# DS8_SCHEMATICv0_1.net
KiCad netlist of a schematic drawn in EAGLE
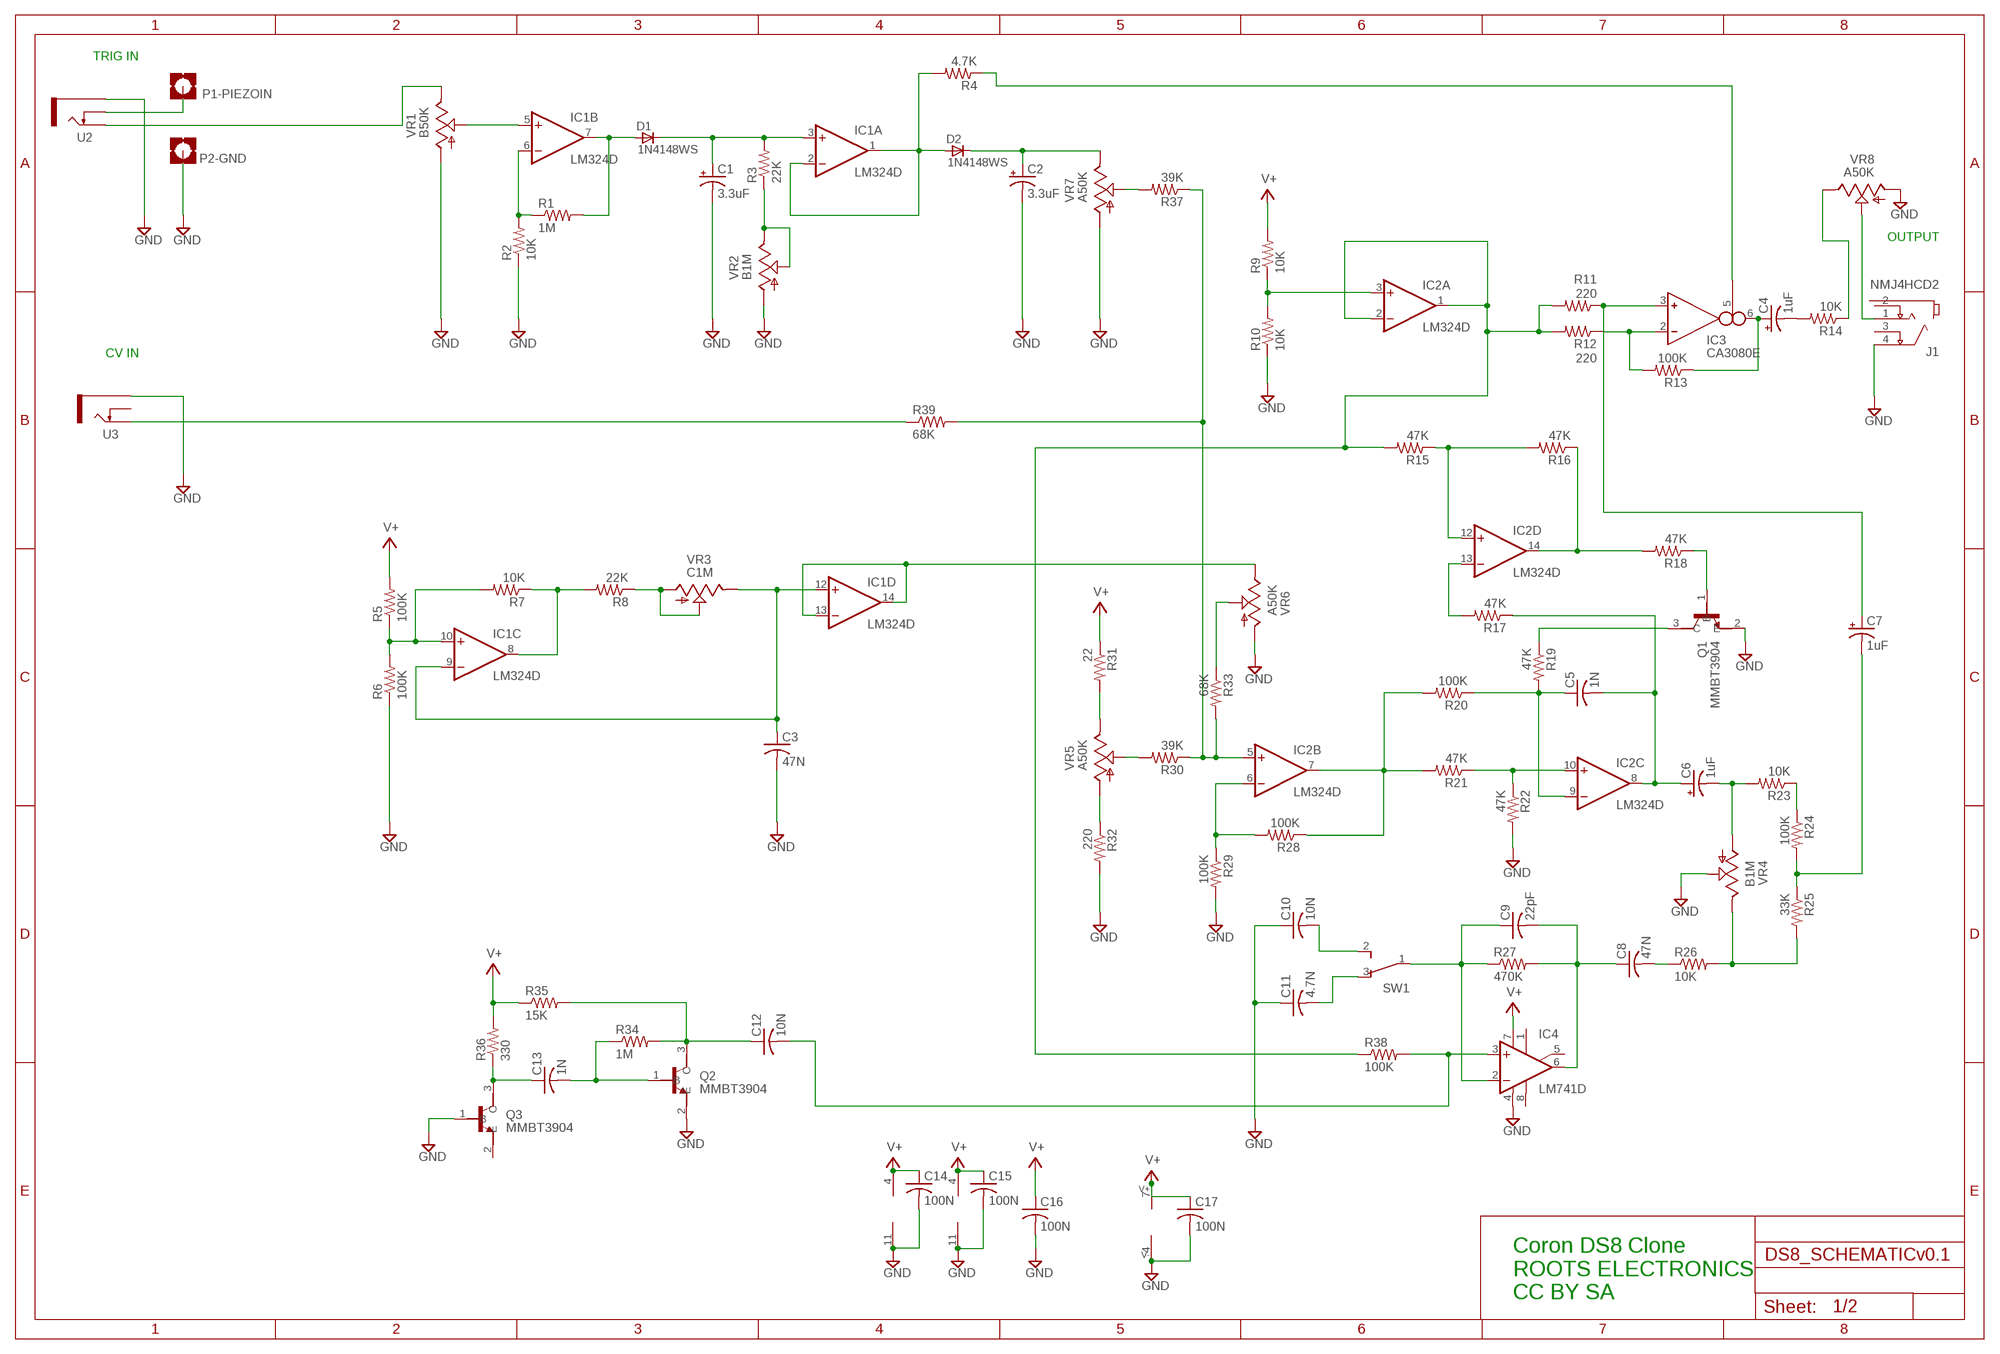
[diagram p0: schematic, sheet 1]
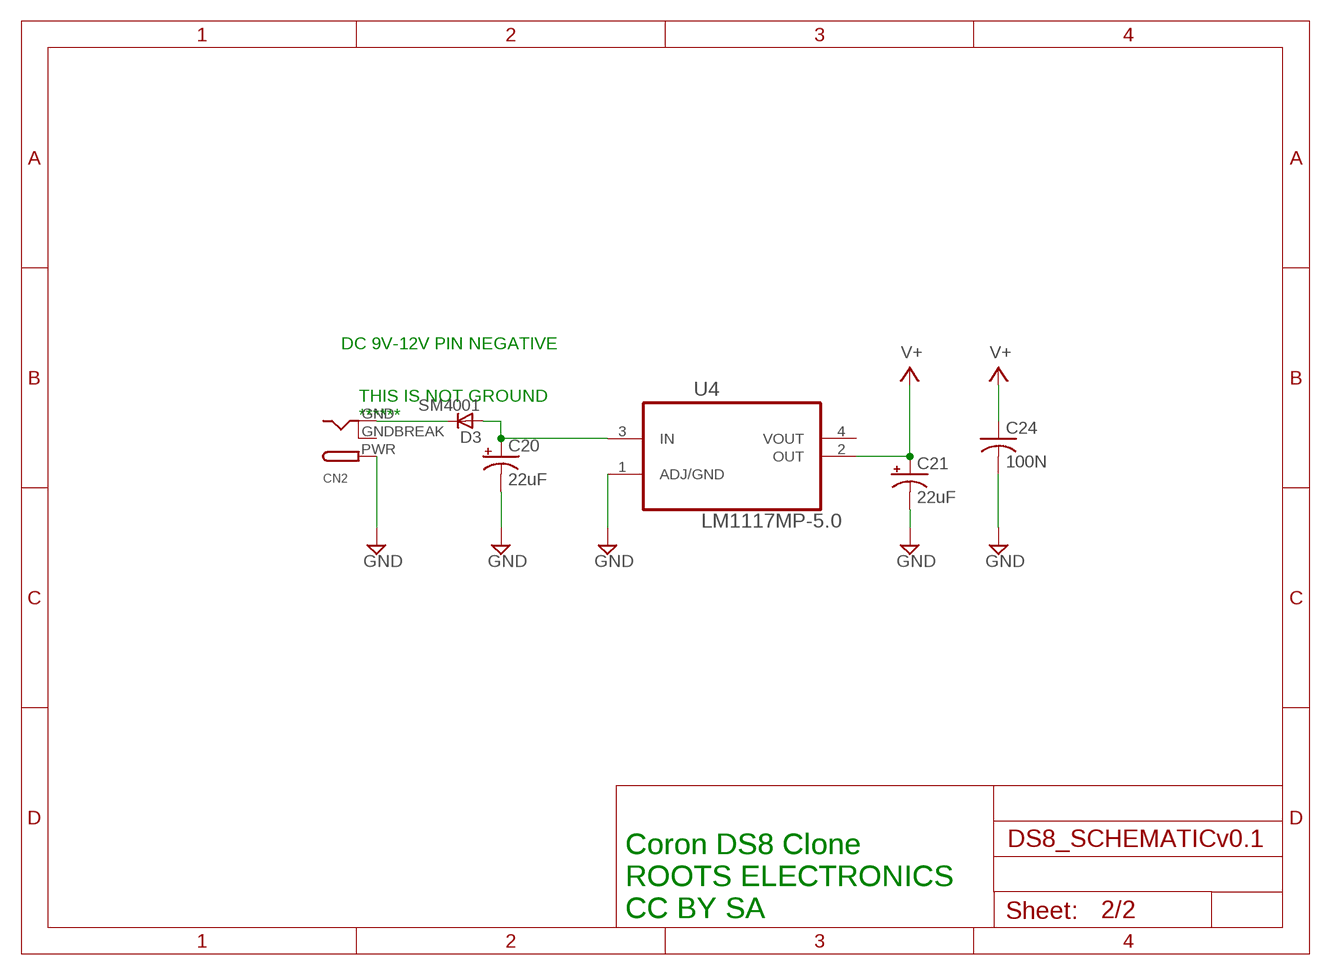
[diagram p1: schematic, sheet 2]

(export (version "E")
  (design (tool "Eeschema 10.0.6"))
  (components
    (comp (ref "C1")
      (value "3.3uF")
      (footprint "eagle-import:PANASONIC_C")
      (libsource (lib "eagle-import") (part "CPOL-USC"))
    )
    (comp (ref "C2")
      (value "3.3uF")
      (footprint "eagle-import:PANASONIC_C")
      (libsource (lib "eagle-import") (part "CPOL-USC"))
    )
    (comp (ref "C3")
      (value "47N")
      (footprint "eagle-import:C0603")
      (libsource (lib "eagle-import") (part "C-USC0603"))
    )
    (comp (ref "C4")
      (value "1uF")
      (footprint "eagle-import:PANASONIC_B")
      (libsource (lib "eagle-import") (part "CPOL-USB"))
    )
    (comp (ref "C5")
      (value "1N")
      (footprint "eagle-import:C0603")
      (libsource (lib "eagle-import") (part "C-USC0603"))
    )
    (comp (ref "C6")
      (value "1uF")
      (footprint "eagle-import:PANASONIC_B")
      (libsource (lib "eagle-import") (part "CPOL-USB"))
    )
    (comp (ref "C7")
      (value "1uF")
      (footprint "eagle-import:PANASONIC_B")
      (libsource (lib "eagle-import") (part "CPOL-USB"))
    )
    (comp (ref "C8")
      (value "47N")
      (footprint "eagle-import:C0603")
      (libsource (lib "eagle-import") (part "C-USC0603"))
    )
    (comp (ref "C9")
      (value "22pF")
      (footprint "eagle-import:C0603")
      (libsource (lib "eagle-import") (part "C-USC0603"))
    )
    (comp (ref "C10")
      (value "10N")
      (footprint "eagle-import:C0603")
      (libsource (lib "eagle-import") (part "C-USC0603"))
    )
    (comp (ref "C11")
      (value "4.7N")
      (footprint "eagle-import:C0603")
      (libsource (lib "eagle-import") (part "C-USC0603"))
    )
    (comp (ref "C12")
      (value "10N")
      (footprint "eagle-import:C0603")
      (libsource (lib "eagle-import") (part "C-USC0603"))
    )
    (comp (ref "C13")
      (value "1N")
      (footprint "eagle-import:C0603")
      (libsource (lib "eagle-import") (part "C-USC0603"))
    )
    (comp (ref "C14")
      (value "100N")
      (footprint "eagle-import:C0603")
      (libsource (lib "eagle-import") (part "C-USC0603"))
    )
    (comp (ref "C15")
      (value "100N")
      (footprint "eagle-import:C0603")
      (libsource (lib "eagle-import") (part "C-USC0603"))
    )
    (comp (ref "C16")
      (value "100N")
      (footprint "eagle-import:C0603")
      (libsource (lib "eagle-import") (part "C-USC0603"))
    )
    (comp (ref "C17")
      (value "100N")
      (footprint "eagle-import:C0603")
      (libsource (lib "eagle-import") (part "C-USC0603"))
    )
    (comp (ref "D1")
      (value "1N4148WS")
      (footprint "eagle-import:SOD323F")
      (libsource (lib "eagle-import") (part "1N4148WS"))
    )
    (comp (ref "D2")
      (value "1N4148WS")
      (footprint "eagle-import:SOD323F")
      (libsource (lib "eagle-import") (part "1N4148WS"))
    )
    (comp (ref "IC1")
      (value "LM324D")
      (footprint "eagle-import:SO14")
      (libsource (lib "eagle-import") (part "LM324D"))
    )
    (comp (ref "IC2")
      (value "LM324D")
      (footprint "eagle-import:SO14")
      (libsource (lib "eagle-import") (part "LM324D"))
    )
    (comp (ref "IC3")
      (value "CA3080E")
      (footprint "eagle-import:DIL08")
      (libsource (lib "eagle-import") (part "CA3080E"))
    )
    (comp (ref "IC4")
      (value "LM741D")
      (footprint "eagle-import:SO08")
      (libsource (lib "eagle-import") (part "741DLM"))
    )
    (comp (ref "J1")
      (value "NMJ4HCD2")
      (footprint "eagle-import:NEUTRIK_NMJ4HCD2")
      (fields (field (name "MF") "Neutrik"))
      (libsource (lib "eagle-import") (part "NMJ4HCD2"))
    )
    (comp (ref "P1-PIEZOIN")
      (value "MOUNT-PAD-SQUARE2.8")
      (footprint "eagle-import:2,8-PAD-SQUARE")
      (libsource (lib "eagle-import") (part "MOUNT-PAD-SQUARE2.8"))
    )
    (comp (ref "P2-GND")
      (value "MOUNT-PAD-SQUARE2.8")
      (footprint "eagle-import:2,8-PAD-SQUARE")
      (libsource (lib "eagle-import") (part "MOUNT-PAD-SQUARE2.8"))
    )
    (comp (ref "Q1")
      (value "MMBT3904")
      (footprint "eagle-import:SOT95P240X120-3N")
      (fields (field (name "MF") "STMicroelectronics"))
      (libsource (lib "eagle-import") (part "MMBT3904"))
    )
    (comp (ref "Q2")
      (value "MMBT3904")
      (footprint "eagle-import:SOT95P240X120-3N")
      (fields (field (name "MF") "STMicroelectronics"))
      (libsource (lib "eagle-import") (part "MMBT3904"))
    )
    (comp (ref "Q3")
      (value "MMBT3904")
      (footprint "eagle-import:SOT95P240X120-3N")
      (fields (field (name "MF") "STMicroelectronics"))
      (libsource (lib "eagle-import") (part "MMBT3904"))
    )
    (comp (ref "R1")
      (value "1M")
      (footprint "eagle-import:R0603")
      (libsource (lib "eagle-import") (part "R-US_R0603"))
    )
    (comp (ref "R2")
      (value "10K")
      (footprint "eagle-import:R0603")
      (libsource (lib "eagle-import") (part "R-US_R0603"))
    )
    (comp (ref "R3")
      (value "22K")
      (footprint "eagle-import:R0603")
      (libsource (lib "eagle-import") (part "R-US_R0603"))
    )
    (comp (ref "R4")
      (value "4.7K")
      (footprint "eagle-import:R0603")
      (libsource (lib "eagle-import") (part "R-US_R0603"))
    )
    (comp (ref "R5")
      (value "100K")
      (footprint "eagle-import:R0603")
      (libsource (lib "eagle-import") (part "R-US_R0603"))
    )
    (comp (ref "R6")
      (value "100K")
      (footprint "eagle-import:R0603")
      (libsource (lib "eagle-import") (part "R-US_R0603"))
    )
    (comp (ref "R7")
      (value "10K")
      (footprint "eagle-import:R0603")
      (libsource (lib "eagle-import") (part "R-US_R0603"))
    )
    (comp (ref "R8")
      (value "22K")
      (footprint "eagle-import:R0603")
      (libsource (lib "eagle-import") (part "R-US_R0603"))
    )
    (comp (ref "R9")
      (value "10K")
      (footprint "eagle-import:R0603")
      (libsource (lib "eagle-import") (part "R-US_R0603"))
    )
    (comp (ref "R10")
      (value "10K")
      (footprint "eagle-import:R0603")
      (libsource (lib "eagle-import") (part "R-US_R0603"))
    )
    (comp (ref "R11")
      (value "220")
      (footprint "eagle-import:R0603")
      (libsource (lib "eagle-import") (part "R-US_R0603"))
    )
    (comp (ref "R12")
      (value "220")
      (footprint "eagle-import:R0603")
      (libsource (lib "eagle-import") (part "R-US_R0603"))
    )
    (comp (ref "R13")
      (value "100K")
      (footprint "eagle-import:R0603")
      (libsource (lib "eagle-import") (part "R-US_R0603"))
    )
    (comp (ref "R14")
      (value "10K")
      (footprint "eagle-import:R0603")
      (libsource (lib "eagle-import") (part "R-US_R0603"))
    )
    (comp (ref "R15")
      (value "47K")
      (footprint "eagle-import:R0603")
      (libsource (lib "eagle-import") (part "R-US_R0603"))
    )
    (comp (ref "R16")
      (value "47K")
      (footprint "eagle-import:R0603")
      (libsource (lib "eagle-import") (part "R-US_R0603"))
    )
    (comp (ref "R17")
      (value "47K")
      (footprint "eagle-import:R0603")
      (libsource (lib "eagle-import") (part "R-US_R0603"))
    )
    (comp (ref "R18")
      (value "47K")
      (footprint "eagle-import:R0603")
      (libsource (lib "eagle-import") (part "R-US_R0603"))
    )
    (comp (ref "R19")
      (value "47K")
      (footprint "eagle-import:R0603")
      (libsource (lib "eagle-import") (part "R-US_R0603"))
    )
    (comp (ref "R20")
      (value "100K")
      (footprint "eagle-import:R0603")
      (libsource (lib "eagle-import") (part "R-US_R0603"))
    )
    (comp (ref "R21")
      (value "47K")
      (footprint "eagle-import:R0603")
      (libsource (lib "eagle-import") (part "R-US_R0603"))
    )
    (comp (ref "R22")
      (value "47K")
      (footprint "eagle-import:R0603")
      (libsource (lib "eagle-import") (part "R-US_R0603"))
    )
    (comp (ref "R23")
      (value "10K")
      (footprint "eagle-import:R0603")
      (libsource (lib "eagle-import") (part "R-US_R0603"))
    )
    (comp (ref "R24")
      (value "100K")
      (footprint "eagle-import:R0603")
      (libsource (lib "eagle-import") (part "R-US_R0603"))
    )
    (comp (ref "R25")
      (value "33K")
      (footprint "eagle-import:R0603")
      (libsource (lib "eagle-import") (part "R-US_R0603"))
    )
    (comp (ref "R26")
      (value "10K")
      (footprint "eagle-import:R0603")
      (libsource (lib "eagle-import") (part "R-US_R0603"))
    )
    (comp (ref "R27")
      (value "470K")
      (footprint "eagle-import:R0603")
      (libsource (lib "eagle-import") (part "R-US_R0603"))
    )
    (comp (ref "R28")
      (value "100K")
      (footprint "eagle-import:R0603")
      (libsource (lib "eagle-import") (part "R-US_R0603"))
    )
    (comp (ref "R29")
      (value "100K")
      (footprint "eagle-import:R0603")
      (libsource (lib "eagle-import") (part "R-US_R0603"))
    )
    (comp (ref "R30")
      (value "39K")
      (footprint "eagle-import:R0603")
      (libsource (lib "eagle-import") (part "R-US_R0603"))
    )
    (comp (ref "R31")
      (value "22")
      (footprint "eagle-import:R0603")
      (libsource (lib "eagle-import") (part "R-US_R0603"))
    )
    (comp (ref "R32")
      (value "220")
      (footprint "eagle-import:R0603")
      (libsource (lib "eagle-import") (part "R-US_R0603"))
    )
    (comp (ref "R33")
      (value "68K")
      (footprint "eagle-import:R0603")
      (libsource (lib "eagle-import") (part "R-US_R0603"))
    )
    (comp (ref "R34")
      (value "1M")
      (footprint "eagle-import:R0603")
      (libsource (lib "eagle-import") (part "R-US_R0603"))
    )
    (comp (ref "R35")
      (value "15K")
      (footprint "eagle-import:R0603")
      (libsource (lib "eagle-import") (part "R-US_R0603"))
    )
    (comp (ref "R36")
      (value "330")
      (footprint "eagle-import:R0603")
      (libsource (lib "eagle-import") (part "R-US_R0603"))
    )
    (comp (ref "R37")
      (value "39K")
      (footprint "eagle-import:R0603")
      (libsource (lib "eagle-import") (part "R-US_R0603"))
    )
    (comp (ref "R38")
      (value "100K")
      (footprint "eagle-import:R0603")
      (libsource (lib "eagle-import") (part "R-US_R0603"))
    )
    (comp (ref "R39")
      (value "68K")
      (footprint "eagle-import:R0603")
      (libsource (lib "eagle-import") (part "R-US_R0603"))
    )
    (comp (ref "SW1")
      (value "450301014042")
      (footprint "eagle-import:450301014042")
      (libsource (lib "eagle-import") (part "450301014042"))
    )
    (comp (ref "U2")
      (value "THONKICONNNEW")
      (footprint "eagle-import:WQP-PJ301M-12_JACK")
      (libsource (lib "eagle-import") (part "THONKICONNNEW"))
    )
    (comp (ref "U3")
      (value "THONKICONNNEW")
      (footprint "eagle-import:WQP-PJ301M-12_JACK")
      (libsource (lib "eagle-import") (part "THONKICONNNEW"))
    )
    (comp (ref "VR1")
      (value "B50K")
      (footprint "eagle-import:9MM_SNAP-IN_POT")
      (libsource (lib "eagle-import") (part "9MM_SNAP-IN_POT_"))
    )
    (comp (ref "VR2")
      (value "B1M")
      (footprint "eagle-import:9MM_SNAP-IN_POT")
      (libsource (lib "eagle-import") (part "9MM_SNAP-IN_POT_"))
    )
    (comp (ref "VR3")
      (value "C1M")
      (footprint "eagle-import:9MM_SNAP-IN_POT")
      (libsource (lib "eagle-import") (part "9MM_SNAP-IN_POT_"))
    )
    (comp (ref "VR4")
      (value "B1M")
      (footprint "eagle-import:9MM_SNAP-IN_POT")
      (libsource (lib "eagle-import") (part "9MM_SNAP-IN_POT_"))
    )
    (comp (ref "VR5")
      (value "A50K")
      (footprint "eagle-import:9MM_SNAP-IN_POT")
      (libsource (lib "eagle-import") (part "9MM_SNAP-IN_POT_"))
    )
    (comp (ref "VR6")
      (value "A50K")
      (footprint "eagle-import:9MM_SNAP-IN_POT")
      (libsource (lib "eagle-import") (part "9MM_SNAP-IN_POT_"))
    )
    (comp (ref "VR7")
      (value "A50K")
      (footprint "eagle-import:9MM_SNAP-IN_POT")
      (libsource (lib "eagle-import") (part "9MM_SNAP-IN_POT_"))
    )
    (comp (ref "VR8")
      (value "A50K")
      (footprint "eagle-import:9MM_SNAP-IN_POT")
      (libsource (lib "eagle-import") (part "9MM_SNAP-IN_POT_"))
    )
    (comp (ref "C20")
      (value "22uF")
      (footprint "eagle-import:PANASONIC_C")
      (libsource (lib "eagle-import") (part "CPOL-USC"))
    )
    (comp (ref "C21")
      (value "22uF")
      (footprint "eagle-import:PANASONIC_C")
      (libsource (lib "eagle-import") (part "CPOL-USC"))
    )
    (comp (ref "C24")
      (value "100N")
      (footprint "eagle-import:C0603")
      (libsource (lib "eagle-import") (part "C-USC0603"))
    )
    (comp (ref "CN2")
      (value "DCBARRELPTH")
      (footprint "eagle-import:DCJACK_2MM_PTH")
      (libsource (lib "eagle-import") (part "DCBARRELPTH"))
    )
    (comp (ref "D3")
      (value "SM4001")
      (footprint "eagle-import:MELF-MLL41_DO213AB")
      (libsource (lib "eagle-import") (part "SM4001"))
    )
    (comp (ref "U4")
      (value "LM1117MP-5.0")
      (footprint "eagle-import:SOT230P696X180-4N")
      (fields (field (name "MF") "Texas Instruments"))
      (libsource (lib "eagle-import") (part "LM1117MP-5.0"))
    )
  )
  (nets
    (net (code "1") (name "GND") (class "Default")
      (node (ref "C1") (pin "-") (pinfunction "-_-") (pintype "passive"))
      (node (ref "C10") (pin "1") (pinfunction "1_1") (pintype "passive"))
      (node (ref "C11") (pin "1") (pinfunction "1_1") (pintype "passive"))
      (node (ref "C14") (pin "2") (pinfunction "2_2") (pintype "passive"))
      (node (ref "C15") (pin "2") (pinfunction "2_2") (pintype "passive"))
      (node (ref "C16") (pin "2") (pinfunction "2_2") (pintype "passive"))
      (node (ref "C17") (pin "2") (pinfunction "2_2") (pintype "passive"))
      (node (ref "C2") (pin "-") (pinfunction "-_-") (pintype "passive"))
      (node (ref "C20") (pin "-") (pinfunction "-_-") (pintype "passive"))
      (node (ref "C21") (pin "-") (pinfunction "-_-") (pintype "passive"))
      (node (ref "C24") (pin "2") (pinfunction "2_2") (pintype "passive"))
      (node (ref "C3") (pin "2") (pinfunction "2_2") (pintype "passive"))
      (node (ref "CN2") (pin "PWR") (pinfunction "PWR_PWR") (pintype "power_in"))
      (node (ref "IC1") (pin "11") (pinfunction "V-_11") (pintype "power_in"))
      (node (ref "IC2") (pin "11") (pinfunction "V-_11") (pintype "power_in"))
      (node (ref "IC3") (pin "4") (pinfunction "V-_4") (pintype "power_in"))
      (node (ref "IC4") (pin "4") (pinfunction "V-_4") (pintype "power_in"))
      (node (ref "J1") (pin "4") (pinfunction "S_4") (pintype "passive"))
      (node (ref "P2-GND") (pin "B2,8") (pinfunction "MOUNT_B2,8") (pintype "passive"))
      (node (ref "Q1") (pin "2") (pinfunction "E_2") (pintype "passive"))
      (node (ref "Q2") (pin "2") (pinfunction "E_2") (pintype "passive"))
      (node (ref "Q3") (pin "1") (pinfunction "B_1") (pintype "passive"))
      (node (ref "R10") (pin "1") (pinfunction "1_1") (pintype "passive"))
      (node (ref "R2") (pin "1") (pinfunction "1_1") (pintype "passive"))
      (node (ref "R22") (pin "2") (pinfunction "2_2") (pintype "passive"))
      (node (ref "R29") (pin "2") (pinfunction "2_2") (pintype "passive"))
      (node (ref "R32") (pin "2") (pinfunction "2_2") (pintype "passive"))
      (node (ref "R6") (pin "1") (pinfunction "1_1") (pintype "passive"))
      (node (ref "U2") (pin "P$3_SLEEVE") (pinfunction "SLEEVE_P$3_SLEEVE") (pintype "passive"))
      (node (ref "U3") (pin "P$3_SLEEVE") (pinfunction "SLEEVE_P$3_SLEEVE") (pintype "passive"))
      (node (ref "U4") (pin "1") (pinfunction "ADJ/GND_1") (pintype "passive"))
      (node (ref "VR1") (pin "1") (pinfunction "A_1") (pintype "passive"))
      (node (ref "VR2") (pin "1") (pinfunction "A_1") (pintype "passive"))
      (node (ref "VR4") (pin "2") (pinfunction "S_2") (pintype "passive"))
      (node (ref "VR6") (pin "1") (pinfunction "A_1") (pintype "passive"))
      (node (ref "VR7") (pin "1") (pinfunction "A_1") (pintype "passive"))
      (node (ref "VR8") (pin "1") (pinfunction "A_1") (pintype "passive"))
    )
    (net (code "2") (name "GNDBREAK") (class "Default")
      (node (ref "CN2") (pin "GNDBREAK") (pinfunction "GNDBREAK_GNDBREAK") (pintype "power_in"))
    )
    (net (code "3") (name "Net-(C4-Pad-)") (class "Default")
      (node (ref "C4") (pin "-") (pinfunction "-_-") (pintype "passive"))
      (node (ref "R14") (pin "2") (pinfunction "2_2") (pintype "passive"))
    )
    (net (code "4") (name "Net-(C7-Pad-)") (class "Default")
      (node (ref "C7") (pin "-") (pinfunction "-_-") (pintype "passive"))
      (node (ref "R24") (pin "2") (pinfunction "2_2") (pintype "passive"))
      (node (ref "R25") (pin "1") (pinfunction "1_1") (pintype "passive"))
    )
    (net (code "5") (name "Net-(C8-Pad2)") (class "Default")
      (node (ref "C8") (pin "2") (pinfunction "2_2") (pintype "passive"))
      (node (ref "R26") (pin "1") (pinfunction "1_1") (pintype "passive"))
    )
    (net (code "6") (name "Net-(C10-Pad2)") (class "Default")
      (node (ref "C10") (pin "2") (pinfunction "2_2") (pintype "passive"))
      (node (ref "SW1") (pin "2") (pinfunction "2_2") (pintype "passive"))
    )
    (net (code "7") (name "Net-(C11-Pad2)") (class "Default")
      (node (ref "C11") (pin "2") (pinfunction "2_2") (pintype "passive"))
      (node (ref "SW1") (pin "3") (pinfunction "3_3") (pintype "passive"))
    )
    (net (code "8") (name "Net-(CN2-PadGND)") (class "Default")
      (node (ref "CN2") (pin "GND") (pinfunction "GND_GND") (pintype "power_in"))
      (node (ref "D3") (pin "C") (pinfunction "C_C") (pintype "passive"))
    )
    (net (code "9") (name "Net-(IC1A-+IN)") (class "Default")
      (node (ref "C1") (pin "+") (pinfunction "+_+") (pintype "passive"))
      (node (ref "D1") (pin "C") (pinfunction "C_C") (pintype "passive"))
      (node (ref "IC1") (pin "3") (pinfunction "+IN_3") (pintype "input"))
      (node (ref "R3") (pin "2") (pinfunction "2_2") (pintype "passive"))
    )
    (net (code "10") (name "Net-(IC1A--IN)") (class "Default")
      (node (ref "D2") (pin "A") (pinfunction "A_A") (pintype "passive"))
      (node (ref "IC1") (pin "1") (pinfunction "OUT_1") (pintype "output"))
      (node (ref "IC1") (pin "2") (pinfunction "-IN_2") (pintype "input"))
      (node (ref "R4") (pin "2") (pinfunction "2_2") (pintype "passive"))
    )
    (net (code "11") (name "Net-(IC1B-+IN)") (class "Default")
      (node (ref "IC1") (pin "5") (pinfunction "+IN_5") (pintype "input"))
      (node (ref "VR1") (pin "2") (pinfunction "S_2") (pintype "passive"))
    )
    (net (code "12") (name "Net-(IC1B--IN)") (class "Default")
      (node (ref "IC1") (pin "6") (pinfunction "-IN_6") (pintype "input"))
      (node (ref "R1") (pin "1") (pinfunction "1_1") (pintype "passive"))
      (node (ref "R2") (pin "2") (pinfunction "2_2") (pintype "passive"))
    )
    (net (code "13") (name "Net-(IC1B-OUT)") (class "Default")
      (node (ref "D1") (pin "A") (pinfunction "A_A") (pintype "passive"))
      (node (ref "IC1") (pin "7") (pinfunction "OUT_7") (pintype "output"))
      (node (ref "R1") (pin "2") (pinfunction "2_2") (pintype "passive"))
    )
    (net (code "14") (name "Net-(IC1C-+IN)") (class "Default")
      (node (ref "IC1") (pin "10") (pinfunction "+IN_10") (pintype "input"))
      (node (ref "R5") (pin "1") (pinfunction "1_1") (pintype "passive"))
      (node (ref "R6") (pin "2") (pinfunction "2_2") (pintype "passive"))
      (node (ref "R7") (pin "2") (pinfunction "2_2") (pintype "passive"))
    )
    (net (code "15") (name "Net-(IC1C--IN)") (class "Default")
      (node (ref "C3") (pin "1") (pinfunction "1_1") (pintype "passive"))
      (node (ref "IC1") (pin "12") (pinfunction "+IN_12") (pintype "input"))
      (node (ref "IC1") (pin "9") (pinfunction "-IN_9") (pintype "input"))
      (node (ref "VR3") (pin "3") (pinfunction "E_3") (pintype "passive"))
    )
    (net (code "16") (name "Net-(IC1C-OUT)") (class "Default")
      (node (ref "IC1") (pin "8") (pinfunction "OUT_8") (pintype "output"))
      (node (ref "R7") (pin "1") (pinfunction "1_1") (pintype "passive"))
      (node (ref "R8") (pin "2") (pinfunction "2_2") (pintype "passive"))
    )
    (net (code "17") (name "Net-(IC1D--IN)") (class "Default")
      (node (ref "IC1") (pin "13") (pinfunction "-IN_13") (pintype "input"))
      (node (ref "IC1") (pin "14") (pinfunction "OUT_14") (pintype "output"))
      (node (ref "VR6") (pin "3") (pinfunction "E_3") (pintype "passive"))
    )
    (net (code "18") (name "Net-(IC2A-+IN)") (class "Default")
      (node (ref "IC2") (pin "3") (pinfunction "+IN_3") (pintype "input"))
      (node (ref "R10") (pin "2") (pinfunction "2_2") (pintype "passive"))
      (node (ref "R9") (pin "1") (pinfunction "1_1") (pintype "passive"))
    )
    (net (code "19") (name "Net-(IC2A--IN)") (class "Default")
      (node (ref "IC2") (pin "1") (pinfunction "OUT_1") (pintype "output"))
      (node (ref "IC2") (pin "2") (pinfunction "-IN_2") (pintype "input"))
      (node (ref "R11") (pin "2") (pinfunction "2_2") (pintype "passive"))
      (node (ref "R12") (pin "2") (pinfunction "2_2") (pintype "passive"))
      (node (ref "R15") (pin "2") (pinfunction "2_2") (pintype "passive"))
      (node (ref "R38") (pin "1") (pinfunction "1_1") (pintype "passive"))
    )
    (net (code "20") (name "Net-(IC2B-+IN)") (class "Default")
      (node (ref "IC2") (pin "5") (pinfunction "+IN_5") (pintype "input"))
      (node (ref "R30") (pin "1") (pinfunction "1_1") (pintype "passive"))
      (node (ref "R33") (pin "2") (pinfunction "2_2") (pintype "passive"))
      (node (ref "R37") (pin "1") (pinfunction "1_1") (pintype "passive"))
      (node (ref "R39") (pin "2") (pinfunction "2_2") (pintype "passive"))
    )
    (net (code "21") (name "Net-(IC2B--IN)") (class "Default")
      (node (ref "IC2") (pin "6") (pinfunction "-IN_6") (pintype "input"))
      (node (ref "R28") (pin "2") (pinfunction "2_2") (pintype "passive"))
      (node (ref "R29") (pin "1") (pinfunction "1_1") (pintype "passive"))
    )
    (net (code "22") (name "Net-(IC2B-OUT)") (class "Default")
      (node (ref "IC2") (pin "7") (pinfunction "OUT_7") (pintype "output"))
      (node (ref "R20") (pin "2") (pinfunction "2_2") (pintype "passive"))
      (node (ref "R21") (pin "2") (pinfunction "2_2") (pintype "passive"))
      (node (ref "R28") (pin "1") (pinfunction "1_1") (pintype "passive"))
    )
    (net (code "23") (name "Net-(IC2C-+IN)") (class "Default")
      (node (ref "IC2") (pin "10") (pinfunction "+IN_10") (pintype "input"))
      (node (ref "R21") (pin "1") (pinfunction "1_1") (pintype "passive"))
      (node (ref "R22") (pin "1") (pinfunction "1_1") (pintype "passive"))
    )
    (net (code "24") (name "Net-(IC2C--IN)") (class "Default")
      (node (ref "C5") (pin "1") (pinfunction "1_1") (pintype "passive"))
      (node (ref "IC2") (pin "9") (pinfunction "-IN_9") (pintype "input"))
      (node (ref "R19") (pin "2") (pinfunction "2_2") (pintype "passive"))
      (node (ref "R20") (pin "1") (pinfunction "1_1") (pintype "passive"))
    )
    (net (code "25") (name "Net-(IC2C-OUT)") (class "Default")
      (node (ref "C5") (pin "2") (pinfunction "2_2") (pintype "passive"))
      (node (ref "C6") (pin "+") (pinfunction "+_+") (pintype "passive"))
      (node (ref "IC2") (pin "8") (pinfunction "OUT_8") (pintype "output"))
      (node (ref "R17") (pin "1") (pinfunction "1_1") (pintype "passive"))
    )
    (net (code "26") (name "Net-(IC2D-+IN)") (class "Default")
      (node (ref "IC2") (pin "12") (pinfunction "+IN_12") (pintype "input"))
      (node (ref "R15") (pin "1") (pinfunction "1_1") (pintype "passive"))
      (node (ref "R16") (pin "2") (pinfunction "2_2") (pintype "passive"))
    )
    (net (code "27") (name "Net-(IC2D--IN)") (class "Default")
      (node (ref "IC2") (pin "13") (pinfunction "-IN_13") (pintype "input"))
      (node (ref "R17") (pin "2") (pinfunction "2_2") (pintype "passive"))
    )
    (net (code "28") (name "Net-(IC2D-OUT)") (class "Default")
      (node (ref "IC2") (pin "14") (pinfunction "OUT_14") (pintype "output"))
      (node (ref "R16") (pin "1") (pinfunction "1_1") (pintype "passive"))
      (node (ref "R18") (pin "2") (pinfunction "2_2") (pintype "passive"))
    )
    (net (code "29") (name "Net-(IC3A-IN_N)") (class "Default")
      (node (ref "IC3") (pin "2") (pinfunction "IN_N_2") (pintype "input"))
      (node (ref "R12") (pin "1") (pinfunction "1_1") (pintype "passive"))
      (node (ref "R13") (pin "2") (pinfunction "2_2") (pintype "passive"))
    )
    (net (code "30") (name "Net-(IC3A-IN_P)") (class "Default")
      (node (ref "C7") (pin "+") (pinfunction "+_+") (pintype "passive"))
      (node (ref "IC3") (pin "3") (pinfunction "IN_P_3") (pintype "input"))
      (node (ref "R11") (pin "1") (pinfunction "1_1") (pintype "passive"))
    )
    (net (code "31") (name "Net-(IC3A-I_BIAS)") (class "Default")
      (node (ref "IC3") (pin "5") (pinfunction "I_BIAS_5") (pintype "input"))
      (node (ref "R4") (pin "1") (pinfunction "1_1") (pintype "passive"))
    )
    (net (code "32") (name "Net-(IC3A-OUT)") (class "Default")
      (node (ref "C4") (pin "+") (pinfunction "+_+") (pintype "passive"))
      (node (ref "IC3") (pin "6") (pinfunction "OUT_6") (pintype "output"))
      (node (ref "R13") (pin "1") (pinfunction "1_1") (pintype "passive"))
    )
    (net (code "33") (name "Net-(IC4-+IN)") (class "Default")
      (node (ref "C12") (pin "2") (pinfunction "2_2") (pintype "passive"))
      (node (ref "IC4") (pin "3") (pinfunction "+IN_3") (pintype "input"))
      (node (ref "R38") (pin "2") (pinfunction "2_2") (pintype "passive"))
    )
    (net (code "34") (name "Net-(IC4--IN)") (class "Default")
      (node (ref "C9") (pin "1") (pinfunction "1_1") (pintype "passive"))
      (node (ref "IC4") (pin "2") (pinfunction "-IN_2") (pintype "input"))
      (node (ref "R27") (pin "1") (pinfunction "1_1") (pintype "passive"))
      (node (ref "SW1") (pin "1") (pinfunction "1_1") (pintype "passive"))
    )
    (net (code "35") (name "Net-(IC4-OUT)") (class "Default")
      (node (ref "C8") (pin "1") (pinfunction "1_1") (pintype "passive"))
      (node (ref "C9") (pin "2") (pinfunction "2_2") (pintype "passive"))
      (node (ref "IC4") (pin "6") (pinfunction "OUT_6") (pintype "output"))
      (node (ref "R27") (pin "2") (pinfunction "2_2") (pintype "passive"))
    )
    (net (code "36") (name "Net-(J1-T)") (class "Default")
      (node (ref "J1") (pin "1") (pinfunction "T_1") (pintype "passive"))
      (node (ref "VR8") (pin "2") (pinfunction "S_2") (pintype "passive"))
    )
    (net (code "37") (name "Net-(P1-PIEZOIN-MOUNT)") (class "Default")
      (node (ref "P1-PIEZOIN") (pin "B2,8") (pinfunction "MOUNT_B2,8") (pintype "passive"))
      (node (ref "U2") (pin "P$2_SWITCH") (pinfunction "SWITCH_P$2_SWITCH") (pintype "passive"))
    )
    (net (code "38") (name "Net-(Q1-B)") (class "Default")
      (node (ref "Q1") (pin "1") (pinfunction "B_1") (pintype "passive"))
      (node (ref "R18") (pin "1") (pinfunction "1_1") (pintype "passive"))
    )
    (net (code "39") (name "Net-(Q1-C)") (class "Default")
      (node (ref "Q1") (pin "3") (pinfunction "C_3") (pintype "passive"))
      (node (ref "R19") (pin "1") (pinfunction "1_1") (pintype "passive"))
    )
    (net (code "40") (name "Net-(Q2-B)") (class "Default")
      (node (ref "C13") (pin "2") (pinfunction "2_2") (pintype "passive"))
      (node (ref "Q2") (pin "1") (pinfunction "B_1") (pintype "passive"))
      (node (ref "R34") (pin "1") (pinfunction "1_1") (pintype "passive"))
    )
    (net (code "41") (name "Net-(Q2-C)") (class "Default")
      (node (ref "C12") (pin "1") (pinfunction "1_1") (pintype "passive"))
      (node (ref "Q2") (pin "3") (pinfunction "C_3") (pintype "passive"))
      (node (ref "R34") (pin "2") (pinfunction "2_2") (pintype "passive"))
      (node (ref "R35") (pin "2") (pinfunction "2_2") (pintype "passive"))
    )
    (net (code "42") (name "Net-(Q3-C)") (class "Default")
      (node (ref "C13") (pin "1") (pinfunction "1_1") (pintype "passive"))
      (node (ref "Q3") (pin "3") (pinfunction "C_3") (pintype "passive"))
      (node (ref "R36") (pin "1") (pinfunction "1_1") (pintype "passive"))
    )
    (net (code "43") (name "Net-(R23-Pad1)") (class "Default")
      (node (ref "R23") (pin "1") (pinfunction "1_1") (pintype "passive"))
      (node (ref "R24") (pin "1") (pinfunction "1_1") (pintype "passive"))
    )
    (net (code "44") (name "Net-(U2-TIP)") (class "Default")
      (node (ref "U2") (pin "P$1_TIP") (pinfunction "TIP_P$1_TIP") (pintype "passive"))
      (node (ref "VR1") (pin "3") (pinfunction "E_3") (pintype "passive"))
    )
    (net (code "45") (name "Net-(U3-TIP)") (class "Default")
      (node (ref "R39") (pin "1") (pinfunction "1_1") (pintype "passive"))
      (node (ref "U3") (pin "P$1_TIP") (pinfunction "TIP_P$1_TIP") (pintype "passive"))
    )
    (net (code "46") (name "Net-(U4-IN)") (class "Default")
      (node (ref "C20") (pin "+") (pinfunction "+_+") (pintype "passive"))
      (node (ref "D3") (pin "A") (pinfunction "A_A") (pintype "passive"))
      (node (ref "U4") (pin "3") (pinfunction "IN_3") (pintype "input"))
    )
    (net (code "47") (name "Net-(VR2-E)") (class "Default")
      (node (ref "R3") (pin "1") (pinfunction "1_1") (pintype "passive"))
      (node (ref "VR2") (pin "2") (pinfunction "S_2") (pintype "passive"))
      (node (ref "VR2") (pin "3") (pinfunction "E_3") (pintype "passive"))
    )
    (net (code "48") (name "Net-(VR3-A)") (class "Default")
      (node (ref "R8") (pin "1") (pinfunction "1_1") (pintype "passive"))
      (node (ref "VR3") (pin "1") (pinfunction "A_1") (pintype "passive"))
      (node (ref "VR3") (pin "2") (pinfunction "S_2") (pintype "passive"))
    )
    (net (code "49") (name "Net-(VR4-A)") (class "Default")
      (node (ref "C6") (pin "-") (pinfunction "-_-") (pintype "passive"))
      (node (ref "R23") (pin "2") (pinfunction "2_2") (pintype "passive"))
      (node (ref "VR4") (pin "1") (pinfunction "A_1") (pintype "passive"))
    )
    (net (code "50") (name "Net-(VR4-E)") (class "Default")
      (node (ref "R25") (pin "2") (pinfunction "2_2") (pintype "passive"))
      (node (ref "R26") (pin "2") (pinfunction "2_2") (pintype "passive"))
      (node (ref "VR4") (pin "3") (pinfunction "E_3") (pintype "passive"))
    )
    (net (code "51") (name "Net-(VR5-A)") (class "Default")
      (node (ref "R32") (pin "1") (pinfunction "1_1") (pintype "passive"))
      (node (ref "VR5") (pin "1") (pinfunction "A_1") (pintype "passive"))
    )
    (net (code "52") (name "Net-(VR5-E)") (class "Default")
      (node (ref "R31") (pin "2") (pinfunction "2_2") (pintype "passive"))
      (node (ref "VR5") (pin "3") (pinfunction "E_3") (pintype "passive"))
    )
    (net (code "53") (name "Net-(VR5-S)") (class "Default")
      (node (ref "R30") (pin "2") (pinfunction "2_2") (pintype "passive"))
      (node (ref "VR5") (pin "2") (pinfunction "S_2") (pintype "passive"))
    )
    (net (code "54") (name "Net-(VR6-S)") (class "Default")
      (node (ref "R33") (pin "1") (pinfunction "1_1") (pintype "passive"))
      (node (ref "VR6") (pin "2") (pinfunction "S_2") (pintype "passive"))
    )
    (net (code "55") (name "Net-(VR7-E)") (class "Default")
      (node (ref "C2") (pin "+") (pinfunction "+_+") (pintype "passive"))
      (node (ref "D2") (pin "C") (pinfunction "C_C") (pintype "passive"))
      (node (ref "VR7") (pin "3") (pinfunction "E_3") (pintype "passive"))
    )
    (net (code "56") (name "Net-(VR7-S)") (class "Default")
      (node (ref "R37") (pin "2") (pinfunction "2_2") (pintype "passive"))
      (node (ref "VR7") (pin "2") (pinfunction "S_2") (pintype "passive"))
    )
    (net (code "57") (name "Net-(VR8-E)") (class "Default")
      (node (ref "R14") (pin "1") (pinfunction "1_1") (pintype "passive"))
      (node (ref "VR8") (pin "3") (pinfunction "E_3") (pintype "passive"))
    )
    (net (code "58") (name "V+") (class "Default")
      (node (ref "C14") (pin "1") (pinfunction "1_1") (pintype "passive"))
      (node (ref "C15") (pin "1") (pinfunction "1_1") (pintype "passive"))
      (node (ref "C16") (pin "1") (pinfunction "1_1") (pintype "passive"))
      (node (ref "C17") (pin "1") (pinfunction "1_1") (pintype "passive"))
      (node (ref "C21") (pin "+") (pinfunction "+_+") (pintype "passive"))
      (node (ref "C24") (pin "1") (pinfunction "1_1") (pintype "passive"))
      (node (ref "IC1") (pin "4") (pinfunction "V+_4") (pintype "power_in"))
      (node (ref "IC2") (pin "4") (pinfunction "V+_4") (pintype "power_in"))
      (node (ref "IC3") (pin "7") (pinfunction "V+_7") (pintype "power_in"))
      (node (ref "IC4") (pin "7") (pinfunction "V+_7") (pintype "power_in"))
      (node (ref "R31") (pin "1") (pinfunction "1_1") (pintype "passive"))
      (node (ref "R35") (pin "1") (pinfunction "1_1") (pintype "passive"))
      (node (ref "R36") (pin "2") (pinfunction "2_2") (pintype "passive"))
      (node (ref "R5") (pin "2") (pinfunction "2_2") (pintype "passive"))
      (node (ref "R9") (pin "2") (pinfunction "2_2") (pintype "passive"))
      (node (ref "U4") (pin "2") (pinfunction "OUT_2") (pintype "output"))
    )
    (net (code "59") (name "unconnected-(IC4-ON1-Pad1)") (class "Default")
      (node (ref "IC4") (pin "1") (pinfunction "ON1_1") (pintype "passive"))
    )
    (net (code "60") (name "unconnected-(IC4-ON2-Pad5)") (class "Default")
      (node (ref "IC4") (pin "5") (pinfunction "ON2_5") (pintype "passive"))
    )
    (net (code "61") (name "unconnected-(IC4-OPT-Pad8)") (class "Default")
      (node (ref "IC4") (pin "8") (pinfunction "OPT_8") (pintype "passive"))
    )
    (net (code "62") (name "unconnected-(J1-SN-Pad3)") (class "Default")
      (node (ref "J1") (pin "3") (pinfunction "SN_3") (pintype "passive"))
    )
    (net (code "63") (name "unconnected-(J1-TN-Pad2)") (class "Default")
      (node (ref "J1") (pin "2") (pinfunction "TN_2") (pintype "passive"))
    )
    (net (code "64") (name "unconnected-(Q3-E-Pad2)") (class "Default")
      (node (ref "Q3") (pin "2") (pinfunction "E_2") (pintype "passive"))
    )
    (net (code "65") (name "unconnected-(U3-SWITCH-PadP$2_SWITCH)") (class "Default")
      (node (ref "U3") (pin "P$2_SWITCH") (pinfunction "SWITCH_P$2_SWITCH") (pintype "passive"))
    )
    (net (code "66") (name "unconnected-(U4-VOUT-Pad4)") (class "Default")
      (node (ref "U4") (pin "4") (pinfunction "VOUT_4") (pintype "output"))
    )
  )
)
